# led_strip-esp32_video_PCB.net
KiCad netlist of a schematic drawn in EAGLE
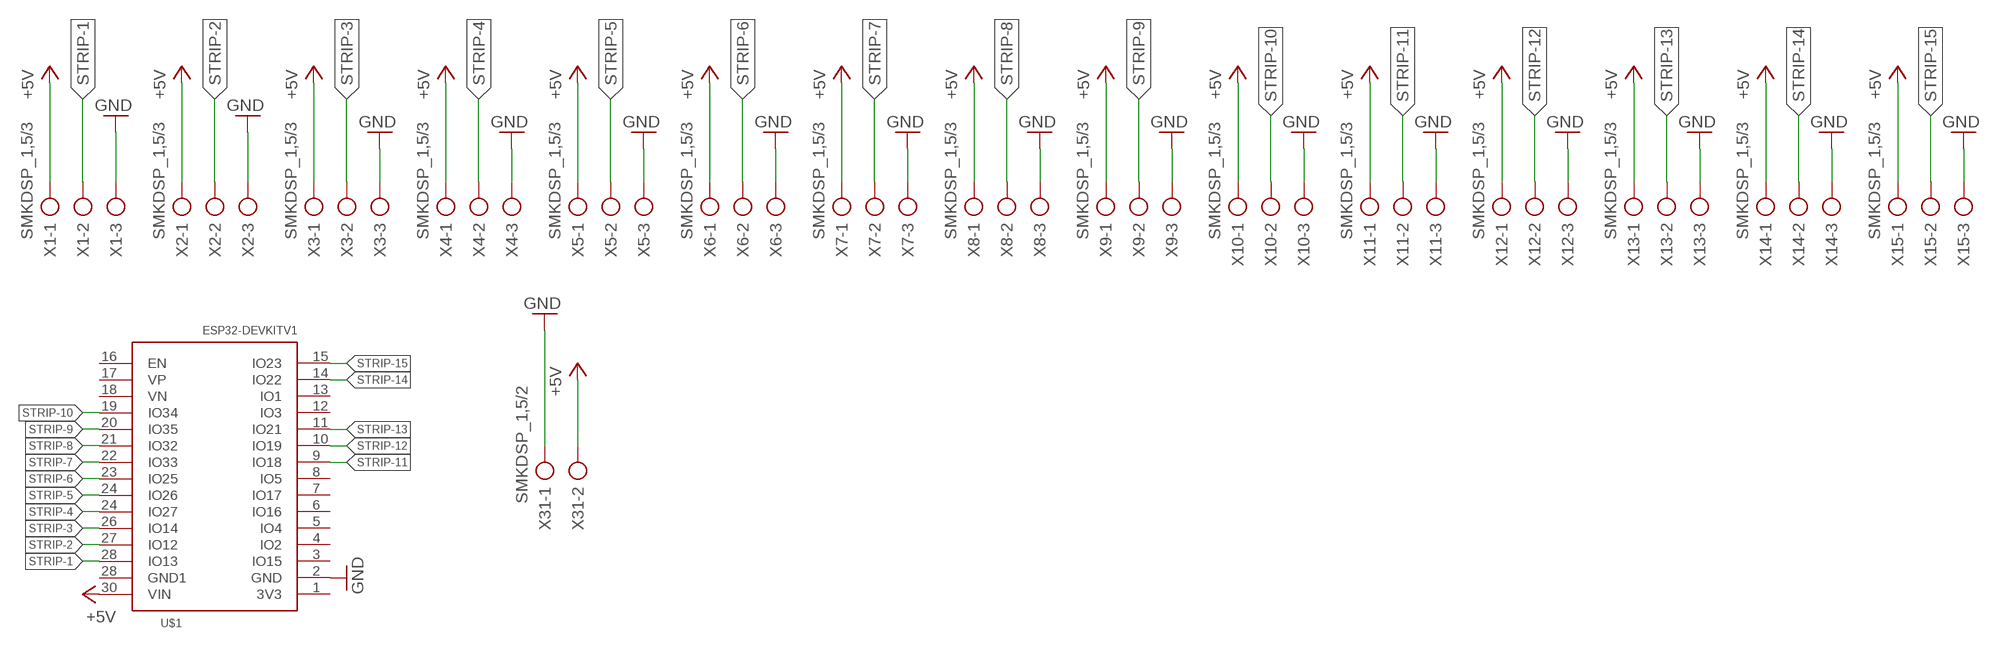
[diagram p0: schematic, sheet 1]

(export (version "E")
  (design (tool "Eeschema 10.0.6"))
  (components
    (comp (ref "U$1")
      (value "ESP32DEVKITV1")
      (footprint "eagle-import:ESP32-DEVKITV1")
      (libsource (lib "eagle-import") (part "ESP32DEVKITV1"))
    )
    (comp (ref "X1")
      (value "SMKDSP_1,5/3")
      (footprint "eagle-import:SMKDSP_1,5_3")
      (fields (field (name "MF") "FARNELL") (field (name "MPN") "1733583"))
      (libsource (lib "eagle-import") (part "SMKDSP_1,5/3"))
    )
    (comp (ref "X2")
      (value "SMKDSP_1,5/3")
      (footprint "eagle-import:SMKDSP_1,5_3")
      (fields (field (name "MF") "FARNELL") (field (name "MPN") "1733583"))
      (libsource (lib "eagle-import") (part "SMKDSP_1,5/3"))
    )
    (comp (ref "X3")
      (value "SMKDSP_1,5/3")
      (footprint "eagle-import:SMKDSP_1,5_3")
      (fields (field (name "MF") "FARNELL") (field (name "MPN") "1733583"))
      (libsource (lib "eagle-import") (part "SMKDSP_1,5/3"))
    )
    (comp (ref "X4")
      (value "SMKDSP_1,5/3")
      (footprint "eagle-import:SMKDSP_1,5_3")
      (fields (field (name "MF") "FARNELL") (field (name "MPN") "1733583"))
      (libsource (lib "eagle-import") (part "SMKDSP_1,5/3"))
    )
    (comp (ref "X5")
      (value "SMKDSP_1,5/3")
      (footprint "eagle-import:SMKDSP_1,5_3")
      (fields (field (name "MF") "FARNELL") (field (name "MPN") "1733583"))
      (libsource (lib "eagle-import") (part "SMKDSP_1,5/3"))
    )
    (comp (ref "X6")
      (value "SMKDSP_1,5/3")
      (footprint "eagle-import:SMKDSP_1,5_3")
      (fields (field (name "MF") "FARNELL") (field (name "MPN") "1733583"))
      (libsource (lib "eagle-import") (part "SMKDSP_1,5/3"))
    )
    (comp (ref "X7")
      (value "SMKDSP_1,5/3")
      (footprint "eagle-import:SMKDSP_1,5_3")
      (fields (field (name "MF") "FARNELL") (field (name "MPN") "1733583"))
      (libsource (lib "eagle-import") (part "SMKDSP_1,5/3"))
    )
    (comp (ref "X8")
      (value "SMKDSP_1,5/3")
      (footprint "eagle-import:SMKDSP_1,5_3")
      (fields (field (name "MF") "FARNELL") (field (name "MPN") "1733583"))
      (libsource (lib "eagle-import") (part "SMKDSP_1,5/3"))
    )
    (comp (ref "X9")
      (value "SMKDSP_1,5/3")
      (footprint "eagle-import:SMKDSP_1,5_3")
      (fields (field (name "MF") "FARNELL") (field (name "MPN") "1733583"))
      (libsource (lib "eagle-import") (part "SMKDSP_1,5/3"))
    )
    (comp (ref "X10")
      (value "SMKDSP_1,5/3")
      (footprint "eagle-import:SMKDSP_1,5_3")
      (fields (field (name "MF") "FARNELL") (field (name "MPN") "1733583"))
      (libsource (lib "eagle-import") (part "SMKDSP_1,5/3"))
    )
    (comp (ref "X11")
      (value "SMKDSP_1,5/3")
      (footprint "eagle-import:SMKDSP_1,5_3")
      (fields (field (name "MF") "FARNELL") (field (name "MPN") "1733583"))
      (libsource (lib "eagle-import") (part "SMKDSP_1,5/3"))
    )
    (comp (ref "X12")
      (value "SMKDSP_1,5/3")
      (footprint "eagle-import:SMKDSP_1,5_3")
      (fields (field (name "MF") "FARNELL") (field (name "MPN") "1733583"))
      (libsource (lib "eagle-import") (part "SMKDSP_1,5/3"))
    )
    (comp (ref "X13")
      (value "SMKDSP_1,5/3")
      (footprint "eagle-import:SMKDSP_1,5_3")
      (fields (field (name "MF") "FARNELL") (field (name "MPN") "1733583"))
      (libsource (lib "eagle-import") (part "SMKDSP_1,5/3"))
    )
    (comp (ref "X14")
      (value "SMKDSP_1,5/3")
      (footprint "eagle-import:SMKDSP_1,5_3")
      (fields (field (name "MF") "FARNELL") (field (name "MPN") "1733583"))
      (libsource (lib "eagle-import") (part "SMKDSP_1,5/3"))
    )
    (comp (ref "X15")
      (value "SMKDSP_1,5/3")
      (footprint "eagle-import:SMKDSP_1,5_3")
      (fields (field (name "MF") "FARNELL") (field (name "MPN") "1733583"))
      (libsource (lib "eagle-import") (part "SMKDSP_1,5/3"))
    )
    (comp (ref "X31")
      (value "SMKDSP_1,5/2")
      (footprint "eagle-import:SMKDSP_1,5_2")
      (fields (field (name "MF") "FARNELL") (field (name "MPN") "1733570"))
      (libsource (lib "eagle-import") (part "SMKDSP_1,5/2"))
    )
  )
  (nets
    (net (code "1") (name "+5V") (class "Default")
      (node (ref "U$1") (pin "30") (pinfunction "VIN_30") (pintype "bidirectional"))
      (node (ref "X1") (pin "1") (pinfunction "KL_1") (pintype "passive"))
      (node (ref "X10") (pin "1") (pinfunction "KL_1") (pintype "passive"))
      (node (ref "X11") (pin "1") (pinfunction "KL_1") (pintype "passive"))
      (node (ref "X12") (pin "1") (pinfunction "KL_1") (pintype "passive"))
      (node (ref "X13") (pin "1") (pinfunction "KL_1") (pintype "passive"))
      (node (ref "X14") (pin "1") (pinfunction "KL_1") (pintype "passive"))
      (node (ref "X15") (pin "1") (pinfunction "KL_1") (pintype "passive"))
      (node (ref "X2") (pin "1") (pinfunction "KL_1") (pintype "passive"))
      (node (ref "X3") (pin "1") (pinfunction "KL_1") (pintype "passive"))
      (node (ref "X31") (pin "2") (pinfunction "KL_2") (pintype "passive"))
      (node (ref "X4") (pin "1") (pinfunction "KL_1") (pintype "passive"))
      (node (ref "X5") (pin "1") (pinfunction "KL_1") (pintype "passive"))
      (node (ref "X6") (pin "1") (pinfunction "KL_1") (pintype "passive"))
      (node (ref "X7") (pin "1") (pinfunction "KL_1") (pintype "passive"))
      (node (ref "X8") (pin "1") (pinfunction "KL_1") (pintype "passive"))
      (node (ref "X9") (pin "1") (pinfunction "KL_1") (pintype "passive"))
    )
    (net (code "2") (name "GND") (class "Default")
      (node (ref "U$1") (pin "2") (pinfunction "GND_2") (pintype "bidirectional"))
      (node (ref "X1") (pin "3") (pinfunction "KL_3") (pintype "passive"))
      (node (ref "X10") (pin "3") (pinfunction "KL_3") (pintype "passive"))
      (node (ref "X11") (pin "3") (pinfunction "KL_3") (pintype "passive"))
      (node (ref "X12") (pin "3") (pinfunction "KL_3") (pintype "passive"))
      (node (ref "X13") (pin "3") (pinfunction "KL_3") (pintype "passive"))
      (node (ref "X14") (pin "3") (pinfunction "KL_3") (pintype "passive"))
      (node (ref "X15") (pin "3") (pinfunction "KL_3") (pintype "passive"))
      (node (ref "X2") (pin "3") (pinfunction "KL_3") (pintype "passive"))
      (node (ref "X3") (pin "3") (pinfunction "KL_3") (pintype "passive"))
      (node (ref "X31") (pin "1") (pinfunction "KL_1") (pintype "passive"))
      (node (ref "X4") (pin "3") (pinfunction "KL_3") (pintype "passive"))
      (node (ref "X5") (pin "3") (pinfunction "KL_3") (pintype "passive"))
      (node (ref "X6") (pin "3") (pinfunction "KL_3") (pintype "passive"))
      (node (ref "X7") (pin "3") (pinfunction "KL_3") (pintype "passive"))
      (node (ref "X8") (pin "3") (pinfunction "KL_3") (pintype "passive"))
      (node (ref "X9") (pin "3") (pinfunction "KL_3") (pintype "passive"))
    )
    (net (code "3") (name "STRIP-1") (class "Default")
      (node (ref "U$1") (pin "28") (pinfunction "IO13_28") (pintype "bidirectional"))
      (node (ref "X1") (pin "2") (pinfunction "KL_2") (pintype "passive"))
    )
    (net (code "4") (name "STRIP-2") (class "Default")
      (node (ref "U$1") (pin "27") (pinfunction "IO12_27") (pintype "bidirectional"))
      (node (ref "X2") (pin "2") (pinfunction "KL_2") (pintype "passive"))
    )
    (net (code "5") (name "STRIP-3") (class "Default")
      (node (ref "U$1") (pin "26") (pinfunction "IO14_26") (pintype "bidirectional"))
      (node (ref "X3") (pin "2") (pinfunction "KL_2") (pintype "passive"))
    )
    (net (code "6") (name "STRIP-4") (class "Default")
      (node (ref "U$1") (pin "24") (pinfunction "IO27_24") (pintype "bidirectional"))
      (node (ref "X4") (pin "2") (pinfunction "KL_2") (pintype "passive"))
    )
    (net (code "7") (name "STRIP-5") (class "Default")
      (node (ref "U$1") (pin "24") (pinfunction "IO26_24") (pintype "bidirectional"))
      (node (ref "X5") (pin "2") (pinfunction "KL_2") (pintype "passive"))
    )
    (net (code "8") (name "STRIP-6") (class "Default")
      (node (ref "U$1") (pin "23") (pinfunction "IO25_23") (pintype "bidirectional"))
      (node (ref "X6") (pin "2") (pinfunction "KL_2") (pintype "passive"))
    )
    (net (code "9") (name "STRIP-7") (class "Default")
      (node (ref "U$1") (pin "22") (pinfunction "IO33_22") (pintype "bidirectional"))
      (node (ref "X7") (pin "2") (pinfunction "KL_2") (pintype "passive"))
    )
    (net (code "10") (name "STRIP-8") (class "Default")
      (node (ref "U$1") (pin "21") (pinfunction "IO32_21") (pintype "bidirectional"))
      (node (ref "X8") (pin "2") (pinfunction "KL_2") (pintype "passive"))
    )
    (net (code "11") (name "STRIP-9") (class "Default")
      (node (ref "U$1") (pin "20") (pinfunction "IO35_20") (pintype "bidirectional"))
      (node (ref "X9") (pin "2") (pinfunction "KL_2") (pintype "passive"))
    )
    (net (code "12") (name "STRIP-10") (class "Default")
      (node (ref "U$1") (pin "19") (pinfunction "IO34_19") (pintype "bidirectional"))
      (node (ref "X10") (pin "2") (pinfunction "KL_2") (pintype "passive"))
    )
    (net (code "13") (name "STRIP-11") (class "Default")
      (node (ref "U$1") (pin "9") (pinfunction "IO18_9") (pintype "bidirectional"))
      (node (ref "X11") (pin "2") (pinfunction "KL_2") (pintype "passive"))
    )
    (net (code "14") (name "STRIP-12") (class "Default")
      (node (ref "U$1") (pin "10") (pinfunction "IO19_10") (pintype "bidirectional"))
      (node (ref "X12") (pin "2") (pinfunction "KL_2") (pintype "passive"))
    )
    (net (code "15") (name "STRIP-13") (class "Default")
      (node (ref "U$1") (pin "11") (pinfunction "IO21_11") (pintype "bidirectional"))
      (node (ref "X13") (pin "2") (pinfunction "KL_2") (pintype "passive"))
    )
    (net (code "16") (name "STRIP-14") (class "Default")
      (node (ref "U$1") (pin "14") (pinfunction "IO22_14") (pintype "bidirectional"))
      (node (ref "X14") (pin "2") (pinfunction "KL_2") (pintype "passive"))
    )
    (net (code "17") (name "STRIP-15") (class "Default")
      (node (ref "U$1") (pin "15") (pinfunction "IO23_15") (pintype "bidirectional"))
      (node (ref "X15") (pin "2") (pinfunction "KL_2") (pintype "passive"))
    )
    (net (code "18") (name "unconnected-(U$1-3V3-Pad1)") (class "Default")
      (node (ref "U$1") (pin "1") (pinfunction "3V3_1") (pintype "bidirectional"))
    )
    (net (code "19") (name "unconnected-(U$1-EN-Pad16)") (class "Default")
      (node (ref "U$1") (pin "16") (pinfunction "EN_16") (pintype "bidirectional"))
    )
    (net (code "20") (name "unconnected-(U$1-GND1-Pad28)") (class "Default")
      (node (ref "U$1") (pin "28") (pinfunction "GND1_28") (pintype "bidirectional"))
    )
    (net (code "21") (name "unconnected-(U$1-IO1-Pad13)") (class "Default")
      (node (ref "U$1") (pin "13") (pinfunction "IO1_13") (pintype "bidirectional"))
    )
    (net (code "22") (name "unconnected-(U$1-IO2-Pad4)") (class "Default")
      (node (ref "U$1") (pin "4") (pinfunction "IO2_4") (pintype "bidirectional"))
    )
    (net (code "23") (name "unconnected-(U$1-IO3-Pad12)") (class "Default")
      (node (ref "U$1") (pin "12") (pinfunction "IO3_12") (pintype "bidirectional"))
    )
    (net (code "24") (name "unconnected-(U$1-IO4-Pad5)") (class "Default")
      (node (ref "U$1") (pin "5") (pinfunction "IO4_5") (pintype "bidirectional"))
    )
    (net (code "25") (name "unconnected-(U$1-IO5-Pad8)") (class "Default")
      (node (ref "U$1") (pin "8") (pinfunction "IO5_8") (pintype "bidirectional"))
    )
    (net (code "26") (name "unconnected-(U$1-IO15-Pad3)") (class "Default")
      (node (ref "U$1") (pin "3") (pinfunction "IO15_3") (pintype "bidirectional"))
    )
    (net (code "27") (name "unconnected-(U$1-IO16-Pad6)") (class "Default")
      (node (ref "U$1") (pin "6") (pinfunction "IO16_6") (pintype "bidirectional"))
    )
    (net (code "28") (name "unconnected-(U$1-IO17-Pad7)") (class "Default")
      (node (ref "U$1") (pin "7") (pinfunction "IO17_7") (pintype "bidirectional"))
    )
    (net (code "29") (name "unconnected-(U$1-VN-Pad18)") (class "Default")
      (node (ref "U$1") (pin "18") (pinfunction "VN_18") (pintype "bidirectional"))
    )
    (net (code "30") (name "unconnected-(U$1-VP-Pad17)") (class "Default")
      (node (ref "U$1") (pin "17") (pinfunction "VP_17") (pintype "bidirectional"))
    )
  )
)
